# white_line.net
KiCad netlist of a schematic drawn in EAGLE
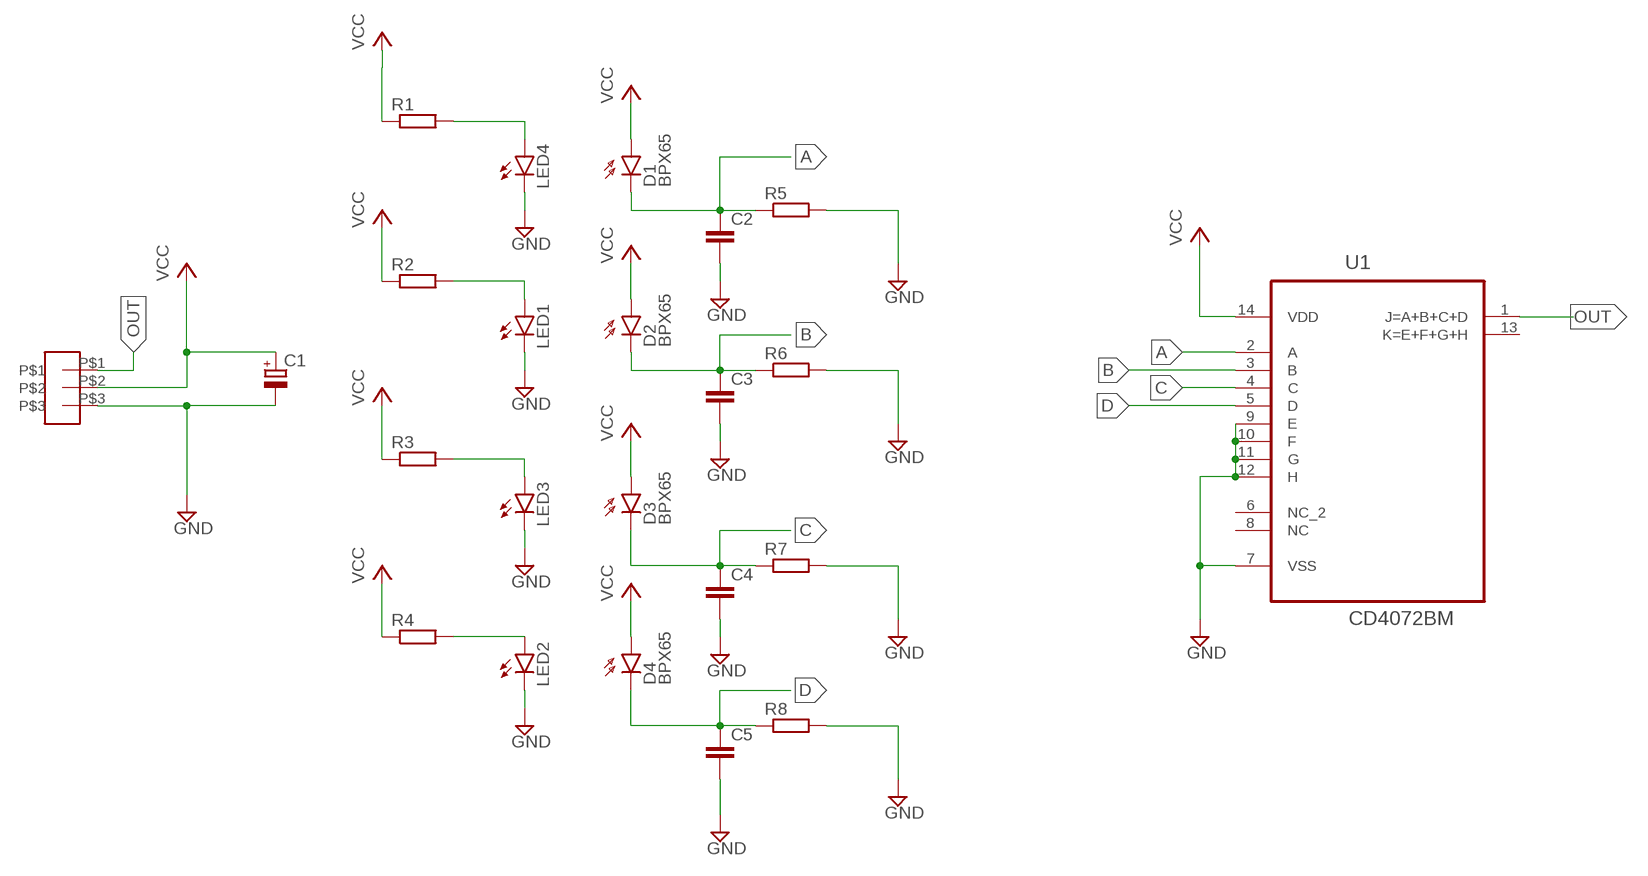
[diagram p0: schematic, sheet 1]

(export (version "E")
  (design (tool "Eeschema 10.0.6"))
  (components
    (comp (ref "3PIN2")
      (value "3PIN")
      (footprint "eagle-import:3PIN")
      (libsource (lib "eagle-import") (part "3PIN"))
    )
    (comp (ref "C1")
      (value "CPOL-EUE2-5")
      (footprint "eagle-import:E2-5")
      (libsource (lib "eagle-import") (part "CPOL-EUE2-5"))
    )
    (comp (ref "C2")
      (value "C-EU050-024X044")
      (footprint "eagle-import:C050-024X044")
      (libsource (lib "eagle-import") (part "C-EU050-024X044"))
    )
    (comp (ref "C3")
      (value "C-EU050-024X044")
      (footprint "eagle-import:C050-024X044")
      (libsource (lib "eagle-import") (part "C-EU050-024X044"))
    )
    (comp (ref "C4")
      (value "C-EU050-024X044")
      (footprint "eagle-import:C050-024X044")
      (libsource (lib "eagle-import") (part "C-EU050-024X044"))
    )
    (comp (ref "C5")
      (value "C-EU050-024X044")
      (footprint "eagle-import:C050-024X044")
      (libsource (lib "eagle-import") (part "C-EU050-024X044"))
    )
    (comp (ref "D1")
      (value "BPX65")
      (footprint "eagle-import:BPX65")
      (fields (field (name "MPN") "BPX65."))
      (libsource (lib "eagle-import") (part "BPX65"))
    )
    (comp (ref "D2")
      (value "BPX65")
      (footprint "eagle-import:BPX65")
      (fields (field (name "MPN") "BPX65."))
      (libsource (lib "eagle-import") (part "BPX65"))
    )
    (comp (ref "D3")
      (value "BPX65")
      (footprint "eagle-import:BPX65")
      (fields (field (name "MPN") "BPX65."))
      (libsource (lib "eagle-import") (part "BPX65"))
    )
    (comp (ref "D4")
      (value "BPX65")
      (footprint "eagle-import:BPX65")
      (fields (field (name "MPN") "BPX65."))
      (libsource (lib "eagle-import") (part "BPX65"))
    )
    (comp (ref "LED1")
      (value "LED3MM")
      (footprint "eagle-import:LED3MM")
      (libsource (lib "eagle-import") (part "LED3MM"))
    )
    (comp (ref "LED2")
      (value "LED3MM")
      (footprint "eagle-import:LED3MM")
      (libsource (lib "eagle-import") (part "LED3MM"))
    )
    (comp (ref "LED3")
      (value "LED3MM")
      (footprint "eagle-import:LED3MM")
      (libsource (lib "eagle-import") (part "LED3MM"))
    )
    (comp (ref "LED4")
      (value "LED3MM")
      (footprint "eagle-import:LED3MM")
      (libsource (lib "eagle-import") (part "LED3MM"))
    )
    (comp (ref "R1")
      (value "R-EU_0204/7")
      (footprint "eagle-import:0204_7")
      (libsource (lib "eagle-import") (part "R-EU_0204/7"))
    )
    (comp (ref "R2")
      (value "R-EU_0204/7")
      (footprint "eagle-import:0204_7")
      (libsource (lib "eagle-import") (part "R-EU_0204/7"))
    )
    (comp (ref "R3")
      (value "R-EU_0204/7")
      (footprint "eagle-import:0204_7")
      (libsource (lib "eagle-import") (part "R-EU_0204/7"))
    )
    (comp (ref "R4")
      (value "R-EU_0204/7")
      (footprint "eagle-import:0204_7")
      (libsource (lib "eagle-import") (part "R-EU_0204/7"))
    )
    (comp (ref "R5")
      (value "R-EU_0204/7")
      (footprint "eagle-import:0204_7")
      (libsource (lib "eagle-import") (part "R-EU_0204/7"))
    )
    (comp (ref "R6")
      (value "R-EU_0204/7")
      (footprint "eagle-import:0204_7")
      (libsource (lib "eagle-import") (part "R-EU_0204/7"))
    )
    (comp (ref "R7")
      (value "R-EU_0204/7")
      (footprint "eagle-import:0204_7")
      (libsource (lib "eagle-import") (part "R-EU_0204/7"))
    )
    (comp (ref "R8")
      (value "R-EU_0204/7")
      (footprint "eagle-import:0204_7")
      (libsource (lib "eagle-import") (part "R-EU_0204/7"))
    )
    (comp (ref "U1")
      (value "CD4072BM")
      (footprint "eagle-import:SOIC127P600X175-14N")
      (fields (field (name "MF") "Texas Instruments"))
      (libsource (lib "eagle-import") (part "CD4072BM"))
    )
  )
  (nets
    (net (code "1") (name "A") (class "Default")
      (node (ref "C2") (pin "1") (pinfunction "1_1") (pintype "passive"))
      (node (ref "D1") (pin "K") (pinfunction "C_K") (pintype "passive"))
      (node (ref "R5") (pin "1") (pinfunction "1_1") (pintype "passive"))
      (node (ref "U1") (pin "2") (pinfunction "A_2") (pintype "input"))
    )
    (net (code "2") (name "B") (class "Default")
      (node (ref "C3") (pin "1") (pinfunction "1_1") (pintype "passive"))
      (node (ref "D2") (pin "K") (pinfunction "C_K") (pintype "passive"))
      (node (ref "R6") (pin "1") (pinfunction "1_1") (pintype "passive"))
      (node (ref "U1") (pin "3") (pinfunction "B_3") (pintype "input"))
    )
    (net (code "3") (name "C") (class "Default")
      (node (ref "C4") (pin "1") (pinfunction "1_1") (pintype "passive"))
      (node (ref "D3") (pin "K") (pinfunction "C_K") (pintype "passive"))
      (node (ref "R7") (pin "1") (pinfunction "1_1") (pintype "passive"))
      (node (ref "U1") (pin "4") (pinfunction "C_4") (pintype "input"))
    )
    (net (code "4") (name "D") (class "Default")
      (node (ref "C5") (pin "1") (pinfunction "1_1") (pintype "passive"))
      (node (ref "D4") (pin "K") (pinfunction "C_K") (pintype "passive"))
      (node (ref "R8") (pin "1") (pinfunction "1_1") (pintype "passive"))
      (node (ref "U1") (pin "5") (pinfunction "D_5") (pintype "input"))
    )
    (net (code "5") (name "GND") (class "Default")
      (node (ref "3PIN2") (pin "P$3") (pinfunction "P$3_P$3") (pintype "bidirectional"))
      (node (ref "C1") (pin "-") (pinfunction "-_-") (pintype "passive"))
      (node (ref "C2") (pin "2") (pinfunction "2_2") (pintype "passive"))
      (node (ref "C3") (pin "2") (pinfunction "2_2") (pintype "passive"))
      (node (ref "C4") (pin "2") (pinfunction "2_2") (pintype "passive"))
      (node (ref "C5") (pin "2") (pinfunction "2_2") (pintype "passive"))
      (node (ref "LED1") (pin "K") (pinfunction "C_K") (pintype "passive"))
      (node (ref "LED2") (pin "K") (pinfunction "C_K") (pintype "passive"))
      (node (ref "LED3") (pin "K") (pinfunction "C_K") (pintype "passive"))
      (node (ref "LED4") (pin "K") (pinfunction "C_K") (pintype "passive"))
      (node (ref "R5") (pin "2") (pinfunction "2_2") (pintype "passive"))
      (node (ref "R6") (pin "2") (pinfunction "2_2") (pintype "passive"))
      (node (ref "R7") (pin "2") (pinfunction "2_2") (pintype "passive"))
      (node (ref "R8") (pin "2") (pinfunction "2_2") (pintype "passive"))
      (node (ref "U1") (pin "10") (pinfunction "F_10") (pintype "input"))
      (node (ref "U1") (pin "11") (pinfunction "G_11") (pintype "input"))
      (node (ref "U1") (pin "12") (pinfunction "H_12") (pintype "input"))
      (node (ref "U1") (pin "7") (pinfunction "VSS_7") (pintype "power_in"))
      (node (ref "U1") (pin "9") (pinfunction "E_9") (pintype "input"))
    )
    (net (code "6") (name "Net-(LED1-PadA)") (class "Default")
      (node (ref "LED1") (pin "A") (pinfunction "A_A") (pintype "passive"))
      (node (ref "R2") (pin "2") (pinfunction "2_2") (pintype "passive"))
    )
    (net (code "7") (name "Net-(LED2-PadA)") (class "Default")
      (node (ref "LED2") (pin "A") (pinfunction "A_A") (pintype "passive"))
      (node (ref "R4") (pin "2") (pinfunction "2_2") (pintype "passive"))
    )
    (net (code "8") (name "Net-(LED3-PadA)") (class "Default")
      (node (ref "LED3") (pin "A") (pinfunction "A_A") (pintype "passive"))
      (node (ref "R3") (pin "2") (pinfunction "2_2") (pintype "passive"))
    )
    (net (code "9") (name "Net-(LED4-PadA)") (class "Default")
      (node (ref "LED4") (pin "A") (pinfunction "A_A") (pintype "passive"))
      (node (ref "R1") (pin "2") (pinfunction "2_2") (pintype "passive"))
    )
    (net (code "10") (name "OUT") (class "Default")
      (node (ref "3PIN2") (pin "P$1") (pinfunction "P$1_P$1") (pintype "bidirectional"))
      (node (ref "U1") (pin "1") (pinfunction "J=A+B+C+D_1") (pintype "output"))
    )
    (net (code "11") (name "VCC") (class "Default")
      (node (ref "3PIN2") (pin "P$2") (pinfunction "P$2_P$2") (pintype "bidirectional"))
      (node (ref "C1") (pin "+") (pinfunction "+_+") (pintype "passive"))
      (node (ref "D1") (pin "A") (pinfunction "A_A") (pintype "passive"))
      (node (ref "D2") (pin "A") (pinfunction "A_A") (pintype "passive"))
      (node (ref "D3") (pin "A") (pinfunction "A_A") (pintype "passive"))
      (node (ref "D4") (pin "A") (pinfunction "A_A") (pintype "passive"))
      (node (ref "R1") (pin "1") (pinfunction "1_1") (pintype "passive"))
      (node (ref "R2") (pin "1") (pinfunction "1_1") (pintype "passive"))
      (node (ref "R3") (pin "1") (pinfunction "1_1") (pintype "passive"))
      (node (ref "R4") (pin "1") (pinfunction "1_1") (pintype "passive"))
      (node (ref "U1") (pin "14") (pinfunction "VDD_14") (pintype "power_in"))
    )
    (net (code "12") (name "unconnected-(U1-K=E+F+G+H-Pad13)") (class "Default")
      (node (ref "U1") (pin "13") (pinfunction "K=E+F+G+H_13") (pintype "output"))
    )
    (net (code "13") (name "unconnected-(U1-NC-Pad8)") (class "Default")
      (node (ref "U1") (pin "8") (pinfunction "NC_8") (pintype "no_connect"))
    )
    (net (code "14") (name "unconnected-(U1-NC_2-Pad6)") (class "Default")
      (node (ref "U1") (pin "6") (pinfunction "NC_2_6") (pintype "no_connect"))
    )
  )
)
